# attiny84_tester-mk-1_0.net
KiCad netlist of a schematic drawn in EAGLE
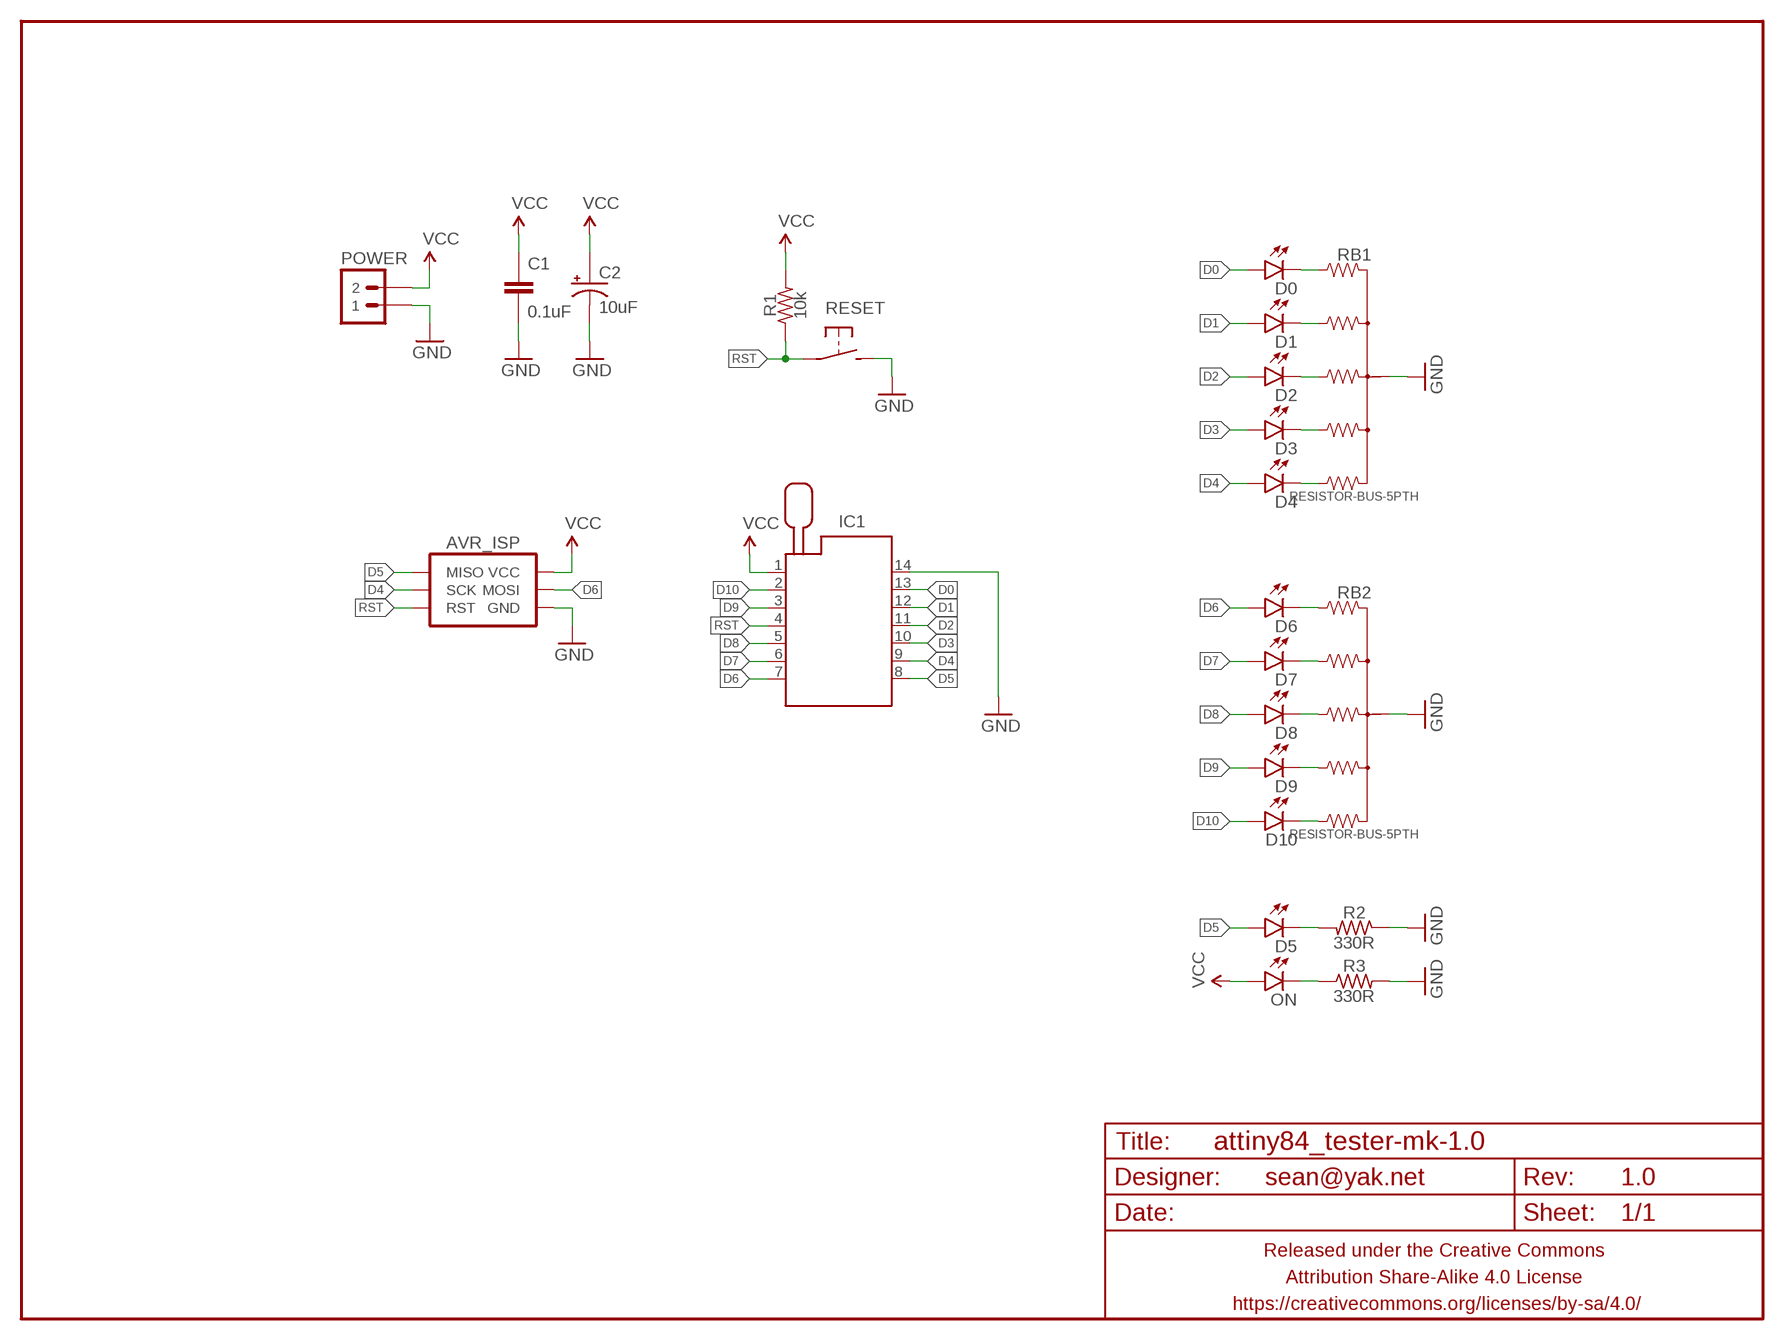
[diagram p0: schematic, sheet 1]

(export (version "E")
  (design (tool "Eeschema 10.0.6"))
  (components
    (comp (ref "AVR_ISP")
      (value "AVR_SPI_PRG_6PTH-SHROUD")
      (footprint "eagle-import:2X3-SHROUDED")
      (libsource (lib "eagle-import") (part "AVR_SPI_PRG_6PTH-SHROUD"))
    )
    (comp (ref "C1")
      (value "0.1uF")
      (footprint "eagle-import:C025-024X044")
      (libsource (lib "eagle-import") (part "CAPACITOR-CERAMIC025-024X044"))
    )
    (comp (ref "C2")
      (value "10uF")
      (footprint "eagle-import:E2-5")
      (libsource (lib "eagle-import") (part "CAPACITOR-POLARIZEDE2-5"))
    )
    (comp (ref "D0")
      (value "LED3MM-LESS")
      (footprint "eagle-import:LED3MM-LESSSILK")
      (libsource (lib "eagle-import") (part "LED3MM-LESS"))
    )
    (comp (ref "D1")
      (value "LED3MM-LESS")
      (footprint "eagle-import:LED3MM-LESSSILK")
      (libsource (lib "eagle-import") (part "LED3MM-LESS"))
    )
    (comp (ref "D2")
      (value "LED3MM-LESS")
      (footprint "eagle-import:LED3MM-LESSSILK")
      (libsource (lib "eagle-import") (part "LED3MM-LESS"))
    )
    (comp (ref "D3")
      (value "LED3MM-LESS")
      (footprint "eagle-import:LED3MM-LESSSILK")
      (libsource (lib "eagle-import") (part "LED3MM-LESS"))
    )
    (comp (ref "D4")
      (value "LED3MM-LESS")
      (footprint "eagle-import:LED3MM-LESSSILK")
      (libsource (lib "eagle-import") (part "LED3MM-LESS"))
    )
    (comp (ref "D5")
      (value "LED3MM-LESS")
      (footprint "eagle-import:LED3MM-LESSSILK")
      (libsource (lib "eagle-import") (part "LED3MM-LESS"))
    )
    (comp (ref "D6")
      (value "LED3MM-LESS")
      (footprint "eagle-import:LED3MM-LESSSILK")
      (libsource (lib "eagle-import") (part "LED3MM-LESS"))
    )
    (comp (ref "D7")
      (value "LED3MM-LESS")
      (footprint "eagle-import:LED3MM-LESSSILK")
      (libsource (lib "eagle-import") (part "LED3MM-LESS"))
    )
    (comp (ref "D8")
      (value "LED3MM-LESS")
      (footprint "eagle-import:LED3MM-LESSSILK")
      (libsource (lib "eagle-import") (part "LED3MM-LESS"))
    )
    (comp (ref "D9")
      (value "LED3MM-LESS")
      (footprint "eagle-import:LED3MM-LESSSILK")
      (libsource (lib "eagle-import") (part "LED3MM-LESS"))
    )
    (comp (ref "D10")
      (value "LED3MM-LESS")
      (footprint "eagle-import:LED3MM-LESSSILK")
      (libsource (lib "eagle-import") (part "LED3MM-LESS"))
    )
    (comp (ref "FRAME1")
      (value "FRAME-LETTERNO_PACKAGE")
      (footprint "eagle-import:DUMMY")
      (fields (field (name "DESIGNER") "sean@yak.net") (field (name "VERSION") "1.0"))
      (libsource (lib "eagle-import") (part "FRAME-LETTERNO_PACKAGE"))
    )
    (comp (ref "IC1")
      (value "ATTiny84")
      (footprint "eagle-import:ZIF14")
      (fields (field (name "MF") "3M") (field (name "MPN") "214-3339-00-0602J"))
      (libsource (lib "eagle-import") (part "ZIF14"))
    )
    (comp (ref "ON")
      (value "LED3MM-LESS")
      (footprint "eagle-import:LED3MM-LESSSILK")
      (libsource (lib "eagle-import") (part "LED3MM-LESS"))
    )
    (comp (ref "POWER")
      (value "M02PTH-CENTERED-R+")
      (footprint "eagle-import:1X02-CENTER-R+")
      (libsource (lib "eagle-import") (part "M02PTH-CENTERED-R+"))
    )
    (comp (ref "R1")
      (value "10k")
      (footprint "eagle-import:RESISTOR-AXIAL-PTH-5.08MM")
      (libsource (lib "eagle-import") (part "RESISTORPTH-AXIAL-5.08MM"))
    )
    (comp (ref "R2")
      (value "330R")
      (footprint "eagle-import:RESISTOR-AXIAL-PTH-5.08MM")
      (libsource (lib "eagle-import") (part "RESISTORPTH-AXIAL-5.08MM"))
    )
    (comp (ref "R3")
      (value "330R")
      (footprint "eagle-import:RESISTOR-AXIAL-PTH-5.08MM")
      (libsource (lib "eagle-import") (part "RESISTORPTH-AXIAL-5.08MM"))
    )
    (comp (ref "RB1")
      (value "RESISTOR-BUS-5PTH")
      (footprint "eagle-import:1X06")
      (libsource (lib "eagle-import") (part "RESISTOR-BUS-5PTH"))
    )
    (comp (ref "RB2")
      (value "RESISTOR-BUS-5PTH")
      (footprint "eagle-import:1X06")
      (libsource (lib "eagle-import") (part "RESISTOR-BUS-5PTH"))
    )
    (comp (ref "RESET")
      (value "SPST-NO-TACT6MM-PTH-SMALL-PADS")
      (footprint "eagle-import:DTS-6-SMALL-PADS")
      (libsource (lib "eagle-import") (part "SPST-NO-TACT6MM-PTH-SMALL-PADS"))
    )
  )
  (nets
    (net (code "1") (name "D0") (class "Default")
      (node (ref "D0") (pin "A") (pinfunction "A_A") (pintype "passive"))
      (node (ref "IC1") (pin "13") (pinfunction "13_13") (pintype "passive"))
    )
    (net (code "2") (name "D1") (class "Default")
      (node (ref "D1") (pin "A") (pinfunction "A_A") (pintype "passive"))
      (node (ref "IC1") (pin "12") (pinfunction "12_12") (pintype "passive"))
    )
    (net (code "3") (name "D2") (class "Default")
      (node (ref "D2") (pin "A") (pinfunction "A_A") (pintype "passive"))
      (node (ref "IC1") (pin "11") (pinfunction "11_11") (pintype "passive"))
    )
    (net (code "4") (name "D3") (class "Default")
      (node (ref "D3") (pin "A") (pinfunction "A_A") (pintype "passive"))
      (node (ref "IC1") (pin "10") (pinfunction "10_10") (pintype "passive"))
    )
    (net (code "5") (name "D4") (class "Default")
      (node (ref "AVR_ISP") (pin "3") (pinfunction "SCK_3") (pintype "passive"))
      (node (ref "D4") (pin "A") (pinfunction "A_A") (pintype "passive"))
      (node (ref "IC1") (pin "9") (pinfunction "9_9") (pintype "passive"))
    )
    (net (code "6") (name "D5") (class "Default")
      (node (ref "AVR_ISP") (pin "1") (pinfunction "MISO_1") (pintype "passive"))
      (node (ref "D5") (pin "A") (pinfunction "A_A") (pintype "passive"))
      (node (ref "IC1") (pin "8") (pinfunction "8_8") (pintype "passive"))
    )
    (net (code "7") (name "D6") (class "Default")
      (node (ref "AVR_ISP") (pin "4") (pinfunction "MOSI_4") (pintype "passive"))
      (node (ref "D6") (pin "A") (pinfunction "A_A") (pintype "passive"))
      (node (ref "IC1") (pin "7") (pinfunction "7_7") (pintype "passive"))
    )
    (net (code "8") (name "D7") (class "Default")
      (node (ref "D7") (pin "A") (pinfunction "A_A") (pintype "passive"))
      (node (ref "IC1") (pin "6") (pinfunction "6_6") (pintype "passive"))
    )
    (net (code "9") (name "D8") (class "Default")
      (node (ref "D8") (pin "A") (pinfunction "A_A") (pintype "passive"))
      (node (ref "IC1") (pin "5") (pinfunction "5_5") (pintype "passive"))
    )
    (net (code "10") (name "D9") (class "Default")
      (node (ref "D9") (pin "A") (pinfunction "A_A") (pintype "passive"))
      (node (ref "IC1") (pin "3") (pinfunction "3_3") (pintype "passive"))
    )
    (net (code "11") (name "D10") (class "Default")
      (node (ref "D10") (pin "A") (pinfunction "A_A") (pintype "passive"))
      (node (ref "IC1") (pin "2") (pinfunction "2_2") (pintype "passive"))
    )
    (net (code "12") (name "GND") (class "Default")
      (node (ref "AVR_ISP") (pin "6") (pinfunction "GND_6") (pintype "passive"))
      (node (ref "C1") (pin "2") (pinfunction "2_2") (pintype "passive"))
      (node (ref "C2") (pin "-") (pinfunction "-_-") (pintype "passive"))
      (node (ref "IC1") (pin "14") (pinfunction "14_14") (pintype "passive"))
      (node (ref "POWER") (pin "1") (pinfunction "1_1") (pintype "passive"))
      (node (ref "R2") (pin "P$1") (pinfunction "1_P$1") (pintype "passive"))
      (node (ref "R3") (pin "P$2") (pinfunction "2_P$2") (pintype "passive"))
      (node (ref "RB1") (pin "6") (pinfunction "COM_6") (pintype "bidirectional"))
      (node (ref "RB2") (pin "6") (pinfunction "COM_6") (pintype "bidirectional"))
      (node (ref "RESET") (pin "3") (pinfunction "2_3") (pintype "passive"))
      (node (ref "RESET") (pin "4") (pinfunction "2_4") (pintype "passive"))
    )
    (net (code "13") (name "Net-(D0-C)") (class "Default")
      (node (ref "D0") (pin "K") (pinfunction "C_K") (pintype "passive"))
      (node (ref "RB1") (pin "1") (pinfunction "1_1") (pintype "bidirectional"))
    )
    (net (code "14") (name "Net-(D1-C)") (class "Default")
      (node (ref "D1") (pin "K") (pinfunction "C_K") (pintype "passive"))
      (node (ref "RB1") (pin "2") (pinfunction "2_2") (pintype "bidirectional"))
    )
    (net (code "15") (name "Net-(D2-C)") (class "Default")
      (node (ref "D2") (pin "K") (pinfunction "C_K") (pintype "passive"))
      (node (ref "RB1") (pin "3") (pinfunction "3_3") (pintype "bidirectional"))
    )
    (net (code "16") (name "Net-(D3-C)") (class "Default")
      (node (ref "D3") (pin "K") (pinfunction "C_K") (pintype "passive"))
      (node (ref "RB1") (pin "4") (pinfunction "4_4") (pintype "bidirectional"))
    )
    (net (code "17") (name "Net-(D4-C)") (class "Default")
      (node (ref "D4") (pin "K") (pinfunction "C_K") (pintype "passive"))
      (node (ref "RB1") (pin "5") (pinfunction "5_5") (pintype "bidirectional"))
    )
    (net (code "18") (name "Net-(D5-C)") (class "Default")
      (node (ref "D5") (pin "K") (pinfunction "C_K") (pintype "passive"))
      (node (ref "R2") (pin "P$2") (pinfunction "2_P$2") (pintype "passive"))
    )
    (net (code "19") (name "Net-(D6-C)") (class "Default")
      (node (ref "D6") (pin "K") (pinfunction "C_K") (pintype "passive"))
      (node (ref "RB2") (pin "1") (pinfunction "1_1") (pintype "bidirectional"))
    )
    (net (code "20") (name "Net-(D7-C)") (class "Default")
      (node (ref "D7") (pin "K") (pinfunction "C_K") (pintype "passive"))
      (node (ref "RB2") (pin "2") (pinfunction "2_2") (pintype "bidirectional"))
    )
    (net (code "21") (name "Net-(D8-C)") (class "Default")
      (node (ref "D8") (pin "K") (pinfunction "C_K") (pintype "passive"))
      (node (ref "RB2") (pin "3") (pinfunction "3_3") (pintype "bidirectional"))
    )
    (net (code "22") (name "Net-(D9-C)") (class "Default")
      (node (ref "D9") (pin "K") (pinfunction "C_K") (pintype "passive"))
      (node (ref "RB2") (pin "4") (pinfunction "4_4") (pintype "bidirectional"))
    )
    (net (code "23") (name "Net-(D10-C)") (class "Default")
      (node (ref "D10") (pin "K") (pinfunction "C_K") (pintype "passive"))
      (node (ref "RB2") (pin "5") (pinfunction "5_5") (pintype "bidirectional"))
    )
    (net (code "24") (name "Net-(ON-C)") (class "Default")
      (node (ref "ON") (pin "K") (pinfunction "C_K") (pintype "passive"))
      (node (ref "R3") (pin "P$1") (pinfunction "1_P$1") (pintype "passive"))
    )
    (net (code "25") (name "RST") (class "Default")
      (node (ref "AVR_ISP") (pin "5") (pinfunction "RST_5") (pintype "passive"))
      (node (ref "IC1") (pin "4") (pinfunction "4_4") (pintype "passive"))
      (node (ref "R1") (pin "P$1") (pinfunction "1_P$1") (pintype "passive"))
      (node (ref "RESET") (pin "1") (pinfunction "1_1") (pintype "passive"))
      (node (ref "RESET") (pin "2") (pinfunction "1_2") (pintype "passive"))
    )
    (net (code "26") (name "VCC") (class "Default")
      (node (ref "AVR_ISP") (pin "2") (pinfunction "VCC_2") (pintype "passive"))
      (node (ref "C1") (pin "1") (pinfunction "1_1") (pintype "passive"))
      (node (ref "C2") (pin "+") (pinfunction "+_+") (pintype "passive"))
      (node (ref "IC1") (pin "1") (pinfunction "1_1") (pintype "passive"))
      (node (ref "ON") (pin "A") (pinfunction "A_A") (pintype "passive"))
      (node (ref "POWER") (pin "2") (pinfunction "2_2") (pintype "passive"))
      (node (ref "R1") (pin "P$2") (pinfunction "2_P$2") (pintype "passive"))
    )
  )
)
